# SVR_REVTT_1_4.net
KiCad netlist of a schematic drawn in Altium Designer
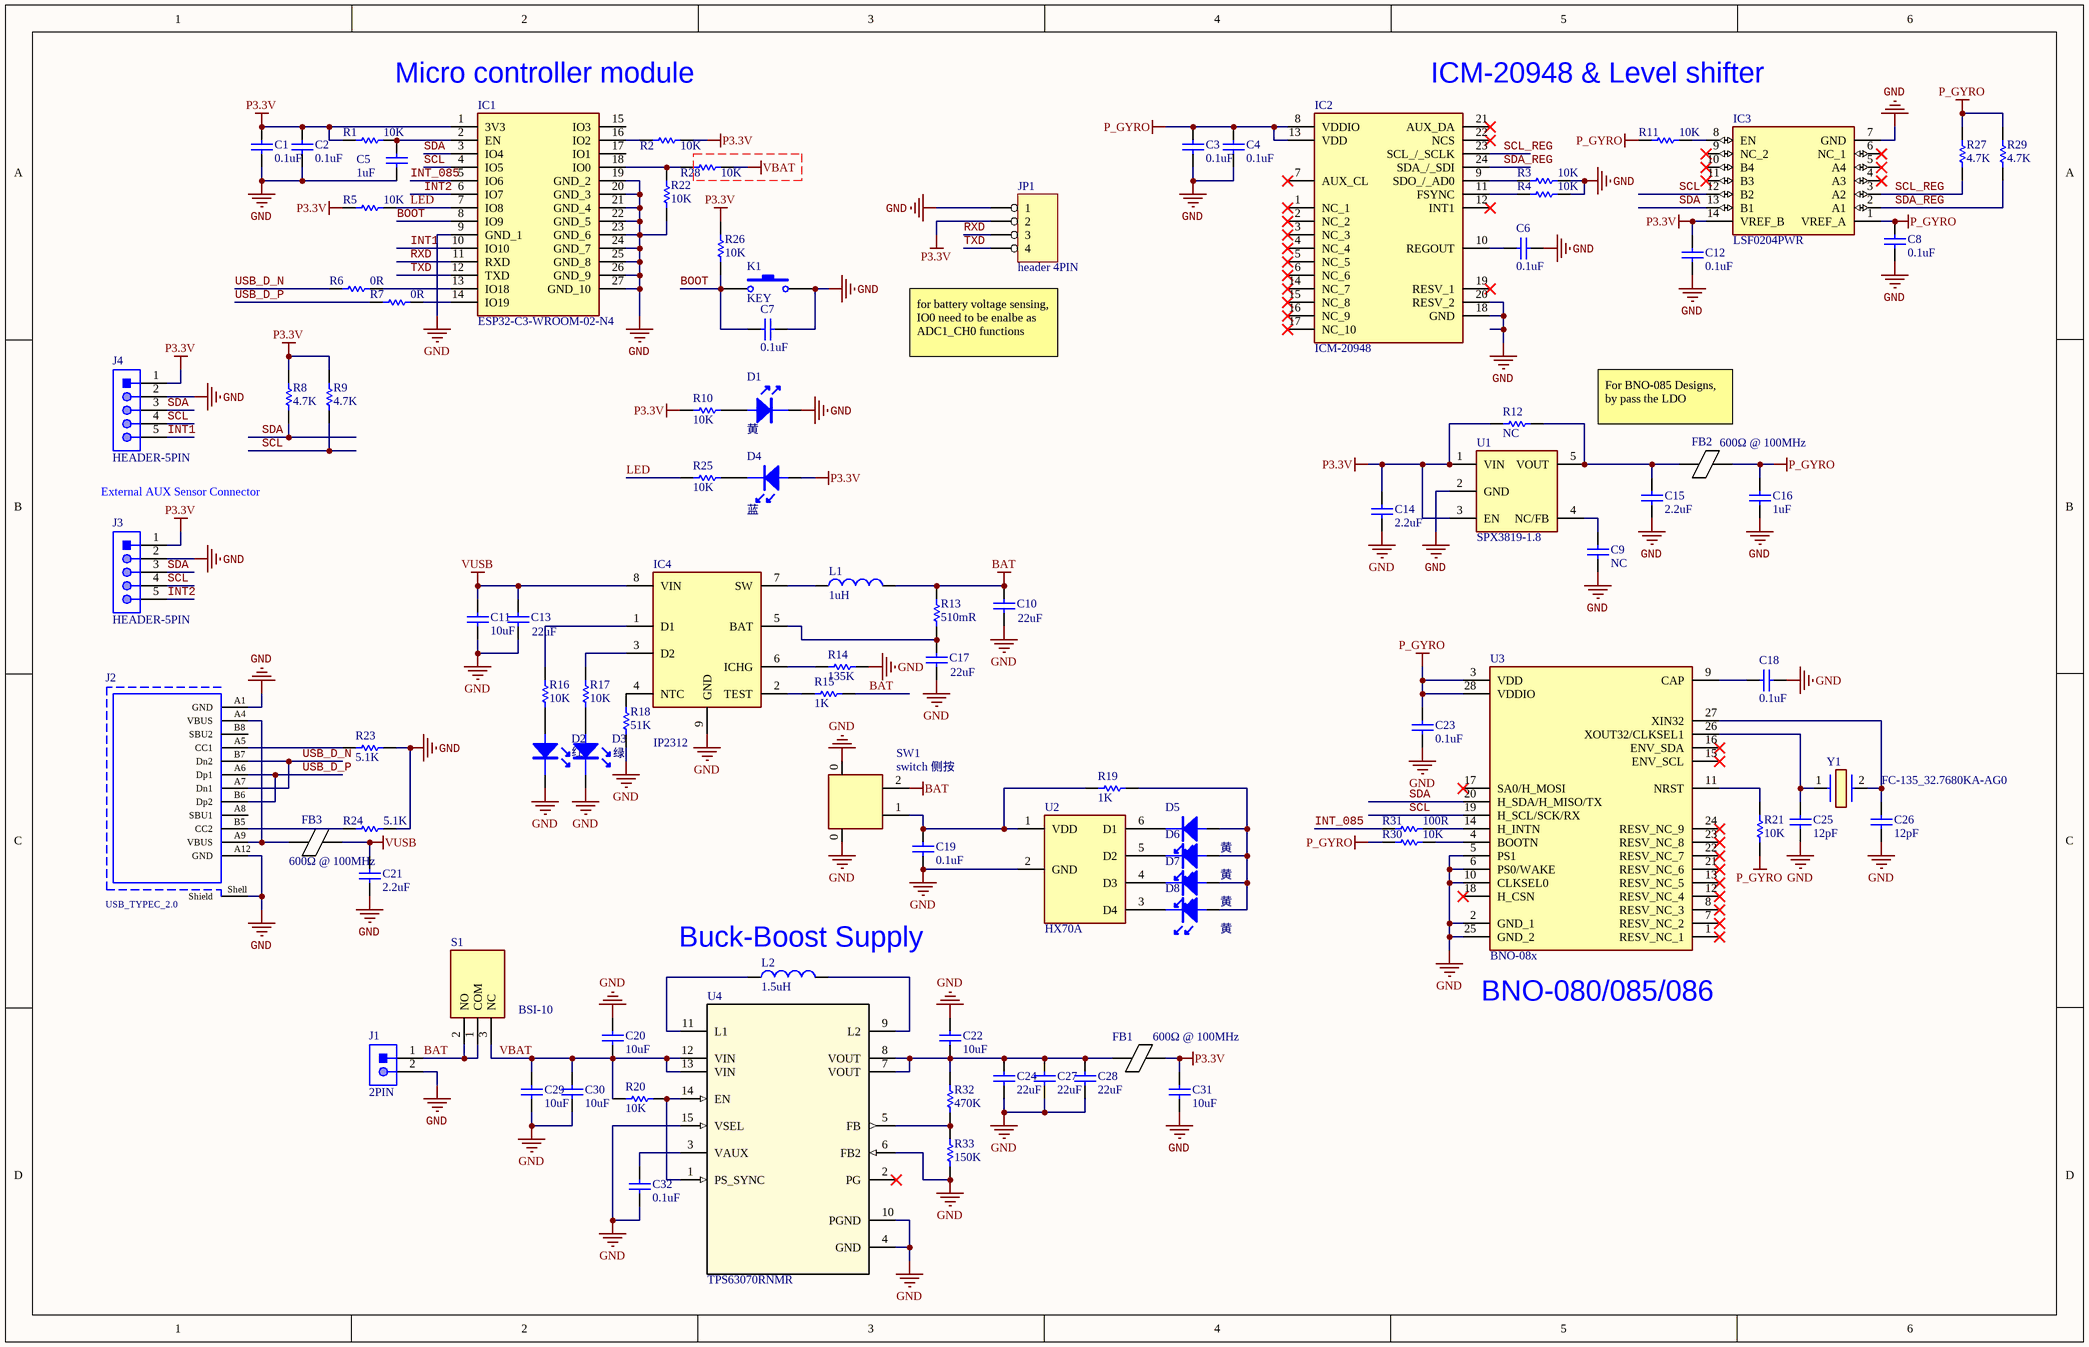
[diagram p0: SVR_REVTT_1.4.SchDoc]

(export (version "E")
  (design (tool "Eeschema 10.0.6"))
  (components
    (comp (ref "C1")
      (value "0.1uF")
      (footprint "0402L")
      (description "Capacitor")
      (fields (field (name "PUBLISHER") "Altium Limited"))
      (libsource (lib "My Footprint") (part "CAP"))
    )
    (comp (ref "C2")
      (value "0.1uF")
      (footprint "0402L")
      (description "Capacitor")
      (fields (field (name "PUBLISHER") "Altium Limited"))
      (libsource (lib "My Footprint") (part "CAP"))
    )
    (comp (ref "C3")
      (value "0.1uF")
      (footprint "0402L")
      (description "Capacitor")
      (fields (field (name "PUBLISHER") "Altium Limited"))
      (libsource (lib "My Footprint") (part "CAP"))
    )
    (comp (ref "C4")
      (value "0.1uF")
      (footprint "0402L")
      (description "Capacitor")
      (fields (field (name "PUBLISHER") "Altium Limited"))
      (libsource (lib "My Footprint") (part "CAP"))
    )
    (comp (ref "C5")
      (value "1uF")
      (footprint "0402L")
      (description "Capacitor")
      (fields (field (name "PUBLISHER") "Altium Limited"))
      (libsource (lib "My Footprint") (part "CAP"))
    )
    (comp (ref "C6")
      (value "0.1uF")
      (footprint "0402L")
      (description "Capacitor")
      (fields (field (name "PUBLISHER") "Altium Limited"))
      (libsource (lib "My Footprint") (part "CAP"))
    )
    (comp (ref "C7")
      (value "0.1uF")
      (footprint "0402L")
      (description "Capacitor")
      (fields (field (name "PUBLISHER") "Altium Limited"))
      (libsource (lib "My Footprint") (part "CAP"))
    )
    (comp (ref "C8")
      (value "0.1uF")
      (footprint "0402L")
      (description "Capacitor")
      (fields (field (name "PUBLISHER") "Altium Limited"))
      (libsource (lib "My Footprint") (part "CAP"))
    )
    (comp (ref "C9")
      (value "NC")
      (footprint "0603_C")
      (description "Capacitor")
      (fields (field (name "PUBLISHER") "Altium Limited"))
      (libsource (lib "My Footprint") (part "CAP"))
    )
    (comp (ref "C10")
      (value "22uF")
      (footprint "0805")
      (description "Capacitor")
      (fields (field (name "PUBLISHER") "Altium Limited"))
      (libsource (lib "My Footprint") (part "CAP"))
    )
    (comp (ref "C11")
      (value "10uF")
      (footprint "0805")
      (description "Capacitor")
      (fields (field (name "PUBLISHER") "Altium Limited"))
      (libsource (lib "My Footprint") (part "CAP"))
    )
    (comp (ref "C12")
      (value "0.1uF")
      (footprint "0402L")
      (description "Capacitor")
      (fields (field (name "PUBLISHER") "Altium Limited"))
      (libsource (lib "My Footprint") (part "CAP"))
    )
    (comp (ref "C13")
      (value "22uF")
      (footprint "0805")
      (description "Capacitor")
      (fields (field (name "PUBLISHER") "Altium Limited"))
      (libsource (lib "My Footprint") (part "CAP"))
    )
    (comp (ref "C14")
      (value "2.2uF")
      (footprint "0603_C")
      (description "Capacitor")
      (fields (field (name "PUBLISHER") "Altium Limited"))
      (libsource (lib "My Footprint") (part "CAP"))
    )
    (comp (ref "C15")
      (value "2.2uF")
      (footprint "0603_C")
      (description "Capacitor")
      (fields (field (name "PUBLISHER") "Altium Limited"))
      (libsource (lib "My Footprint") (part "CAP"))
    )
    (comp (ref "C16")
      (value "1uF")
      (footprint "0603_C")
      (description "Capacitor")
      (fields (field (name "PUBLISHER") "Altium Limited"))
      (libsource (lib "My Footprint") (part "CAP"))
    )
    (comp (ref "C17")
      (value "22uF")
      (footprint "0805")
      (description "Capacitor")
      (fields (field (name "PUBLISHER") "Altium Limited"))
      (libsource (lib "My Footprint") (part "CAP"))
    )
    (comp (ref "C18")
      (value "0.1uF")
      (footprint "0402L")
      (description "Capacitor")
      (fields (field (name "PUBLISHER") "Altium Limited"))
      (libsource (lib "My Footprint") (part "CAP"))
    )
    (comp (ref "C19")
      (value "0.1uF")
      (footprint "0402L")
      (description "Capacitor")
      (fields (field (name "PUBLISHER") "Altium Limited"))
      (libsource (lib "My Footprint") (part "CAP"))
    )
    (comp (ref "C20")
      (value "10uF")
      (footprint "0603_C")
      (description "Capacitor")
      (fields (field (name "PUBLISHER") "Altium Limited"))
      (libsource (lib "My Footprint") (part "CAP"))
    )
    (comp (ref "C21")
      (value "2.2uF")
      (footprint "0603_C")
      (description "Capacitor")
      (fields (field (name "PUBLISHER") "Altium Limited"))
      (libsource (lib "My Footprint") (part "CAP"))
    )
    (comp (ref "C22")
      (value "10uF")
      (footprint "0603_C")
      (description "Capacitor")
      (fields (field (name "PUBLISHER") "Altium Limited"))
      (libsource (lib "My Footprint") (part "CAP"))
    )
    (comp (ref "C23")
      (value "0.1uF")
      (footprint "0402L")
      (description "Capacitor")
      (fields (field (name "PUBLISHER") "Altium Limited"))
      (libsource (lib "My Footprint") (part "CAP"))
    )
    (comp (ref "C24")
      (value "22uF")
      (footprint "0805")
      (description "Capacitor")
      (fields (field (name "PUBLISHER") "Altium Limited"))
      (libsource (lib "My Footprint") (part "CAP"))
    )
    (comp (ref "C25")
      (value "12pF")
      (footprint "0402L")
      (description "Capacitor")
      (fields (field (name "PUBLISHER") "Altium Limited"))
      (libsource (lib "My Footprint") (part "CAP"))
    )
    (comp (ref "C26")
      (value "12pF")
      (footprint "0402L")
      (description "Capacitor")
      (fields (field (name "PUBLISHER") "Altium Limited"))
      (libsource (lib "My Footprint") (part "CAP"))
    )
    (comp (ref "C27")
      (value "22uF")
      (footprint "0805")
      (description "Capacitor")
      (fields (field (name "PUBLISHER") "Altium Limited"))
      (libsource (lib "My Footprint") (part "CAP"))
    )
    (comp (ref "C28")
      (value "22uF")
      (footprint "0805")
      (description "Capacitor")
      (fields (field (name "PUBLISHER") "Altium Limited"))
      (libsource (lib "My Footprint") (part "CAP"))
    )
    (comp (ref "C29")
      (value "10uF")
      (footprint "0805")
      (description "Capacitor")
      (fields (field (name "PUBLISHER") "Altium Limited"))
      (libsource (lib "My Footprint") (part "CAP"))
    )
    (comp (ref "C30")
      (value "10uF")
      (footprint "0805")
      (description "Capacitor")
      (fields (field (name "PUBLISHER") "Altium Limited"))
      (libsource (lib "My Footprint") (part "CAP"))
    )
    (comp (ref "C31")
      (value "10uF")
      (footprint "0805")
      (description "Capacitor")
      (fields (field (name "PUBLISHER") "Altium Limited"))
      (libsource (lib "My Footprint") (part "CAP"))
    )
    (comp (ref "C32")
      (value "0.1uF")
      (footprint "0402L")
      (description "Capacitor")
      (fields (field (name "PUBLISHER") "Altium Limited"))
      (libsource (lib "My Footprint") (part "CAP"))
    )
    (comp (ref "D1")
      (value "黄")
      (footprint "0603_LED")
      (description "LED 发光二极管")
      (libsource (lib "My Footprint") (part "LED"))
    )
    (comp (ref "D2")
      (value "红")
      (footprint "0603_LED")
      (description "LED 发光二极管")
      (libsource (lib "My Footprint") (part "LED"))
    )
    (comp (ref "D3")
      (value "绿")
      (footprint "0603_LED")
      (description "LED 发光二极管")
      (libsource (lib "My Footprint") (part "LED"))
    )
    (comp (ref "D4")
      (value "蓝")
      (footprint "0603_LED")
      (description "LED 发光二极管")
      (libsource (lib "") (part "LED_1"))
    )
    (comp (ref "D5")
      (value "黄")
      (footprint "0603_LED")
      (description "LED 发光二极管")
      (libsource (lib "My Footprint") (part "LED"))
    )
    (comp (ref "D6")
      (value "黄")
      (footprint "0603_LED")
      (description "LED 发光二极管")
      (libsource (lib "My Footprint") (part "LED"))
    )
    (comp (ref "D7")
      (value "黄")
      (footprint "0603_LED")
      (description "LED 发光二极管")
      (libsource (lib "My Footprint") (part "LED"))
    )
    (comp (ref "D8")
      (value "黄")
      (footprint "0603_LED")
      (description "LED 发光二极管")
      (libsource (lib "My Footprint") (part "LED"))
    )
    (comp (ref "FB1")
      (value "600Ω @ 100MHz")
      (footprint "0805")
      (description "磁珠 600Ω @ 100MHz")
      (libsource (lib "My Footprint") (part "FB"))
    )
    (comp (ref "FB2")
      (value "600Ω @ 100MHz")
      (footprint "0603")
      (description "磁珠 600Ω @ 100MHz")
      (libsource (lib "My Footprint") (part "FB"))
    )
    (comp (ref "FB3")
      (value "600Ω @ 100MHz")
      (footprint "0603")
      (description "磁珠 600Ω @ 100MHz")
      (libsource (lib "My Footprint") (part "FB"))
    )
    (comp (ref "IC1")
      (value "ESP32-C3-WROOM-02-N4")
      (footprint "SamacSys:ESP32C3WROOM02N4")
      (description "Integrated Circuit")
      (fields (field (name "MOUSER PART NUMBER") "356-ESP32C3WROOM02N4"))
      (libsource (lib "SamacSys") (part "ESP32-C3-WROOM-02-N4"))
    )
    (comp (ref "IC2")
      (value "ICM-20948")
      (footprint "SamacSys:QFN40P300X300X105-25N-D")
      (description "Integrated Circuit")
      (fields (field (name "MOUSER PART NUMBER") "410-ICM-20948"))
      (libsource (lib "SamacSys") (part "ICM-20948"))
    )
    (comp (ref "IC3")
      (value "LSF0204PWR")
      (footprint "SamacSys:SOP65P640X120-14N")
      (description "Integrated Circuit")
      (fields (field (name "MOUSER PART NUMBER") "595-LSF0204PWR"))
      (libsource (lib "SamacSys") (part "LSF0204PWR"))
    )
    (comp (ref "IC4")
      (value "IP2312")
      (footprint "SOIC-8N")
      (description "Integrated Circuit")
      (libsource (lib "SamacSys") (part "IP2312"))
    )
    (comp (ref "J1")
      (value "2PIN")
      (footprint "XH2.54-WI-2P")
      (libsource (lib "My Footprint") (part "HEADER 2PIN"))
    )
    (comp (ref "J2")
      (value "USB_TYPEC_2.0")
      (footprint "USB_TYPEC_2.0_Horizontal_SMT")
      (description "USB 3.1 Type C Receptacle WR-COM, Horizontal, SMT / THT")
      (fields (field (name "PART NUMBER") "632723300011") (field (name "PUBLISHER") "Wurth Elektronik"))
      (libsource (lib "RegenovoPcbLib") (part "USB_TYPEC_2.0"))
    )
    (comp (ref "J3")
      (value "HEADER-5PIN")
      (footprint "HEADER_5P_1.25_RT")
      (libsource (lib "My Footprint") (part "HEADER-5PIN"))
    )
    (comp (ref "J4")
      (value "HEADER-5PIN")
      (footprint "HEADER_5P_1.25_RT")
      (libsource (lib "My Footprint") (part "HEADER-5PIN"))
    )
    (comp (ref "JP1")
      (value "header 4PIN")
      (footprint "header4")
      (libsource (lib "My Footprint") (part "HEADER 4"))
    )
    (comp (ref "K1")
      (value "KEY")
      (footprint "KEY_2")
      (description "Switch")
      (fields (field (name "PUBLISHER") "Altium Limited"))
      (libsource (lib "My Footprint") (part "KEY_2"))
    )
    (comp (ref "L1")
      (value "1uH")
      (footprint "Inductor  SLO0650")
      (description "电感")
      (fields (field (name "Comment") "INDUCTOR") (field (name "PUBLISHER") "Altium Limited"))
      (libsource (lib "RegenovoPcbLib") (part "INDUCTOR"))
    )
    (comp (ref "L2")
      (value "1.5uH")
      (footprint "Inductor  SMNR4020")
      (description "电感")
      (fields (field (name "Comment") "INDUCTOR") (field (name "PUBLISHER") "Altium Limited"))
      (libsource (lib "RegenovoPcbLib") (part "INDUCTOR"))
    )
    (comp (ref "R1")
      (value "10K")
      (footprint "0402L")
      (description "Resistor")
      (fields (field (name "PUBLISHER") "Altium Limited"))
      (libsource (lib "My Footprint") (part "RES"))
    )
    (comp (ref "R2")
      (value "10K")
      (footprint "0402L")
      (description "Resistor")
      (fields (field (name "PUBLISHER") "Altium Limited"))
      (libsource (lib "My Footprint") (part "RES"))
    )
    (comp (ref "R3")
      (value "10K")
      (footprint "0402L")
      (description "Resistor")
      (fields (field (name "PUBLISHER") "Altium Limited"))
      (libsource (lib "My Footprint") (part "RES"))
    )
    (comp (ref "R4")
      (value "10K")
      (footprint "0402L")
      (description "Resistor")
      (fields (field (name "PUBLISHER") "Altium Limited"))
      (libsource (lib "My Footprint") (part "RES"))
    )
    (comp (ref "R5")
      (value "10K")
      (footprint "0402L")
      (description "Resistor")
      (fields (field (name "PUBLISHER") "Altium Limited"))
      (libsource (lib "My Footprint") (part "RES"))
    )
    (comp (ref "R6")
      (value "0R")
      (footprint "0402L")
      (description "Resistor")
      (fields (field (name "PUBLISHER") "Altium Limited"))
      (libsource (lib "My Footprint") (part "RES"))
    )
    (comp (ref "R7")
      (value "0R")
      (footprint "0402L")
      (description "Resistor")
      (fields (field (name "PUBLISHER") "Altium Limited"))
      (libsource (lib "My Footprint") (part "RES"))
    )
    (comp (ref "R8")
      (value "4.7K")
      (footprint "0402L")
      (description "Resistor")
      (fields (field (name "PUBLISHER") "Altium Limited"))
      (libsource (lib "My Footprint") (part "RES"))
    )
    (comp (ref "R9")
      (value "4.7K")
      (footprint "0402L")
      (description "Resistor")
      (fields (field (name "PUBLISHER") "Altium Limited"))
      (libsource (lib "My Footprint") (part "RES"))
    )
    (comp (ref "R10")
      (value "10K")
      (footprint "0402L")
      (description "Resistor")
      (fields (field (name "PUBLISHER") "Altium Limited"))
      (libsource (lib "My Footprint") (part "RES"))
    )
    (comp (ref "R11")
      (value "10K")
      (footprint "0402L")
      (description "Resistor")
      (fields (field (name "PUBLISHER") "Altium Limited"))
      (libsource (lib "My Footprint") (part "RES"))
    )
    (comp (ref "R12")
      (value "NC")
      (footprint "0603")
      (description "Resistor")
      (fields (field (name "PUBLISHER") "Altium Limited"))
      (libsource (lib "My Footprint") (part "RES"))
    )
    (comp (ref "R13")
      (value "510mR")
      (footprint "0603L")
      (description "Resistor")
      (fields (field (name "PUBLISHER") "Altium Limited"))
      (libsource (lib "My Footprint") (part "RES"))
    )
    (comp (ref "R14")
      (value "135K")
      (footprint "0402L")
      (description "Resistor")
      (fields (field (name "PUBLISHER") "Altium Limited"))
      (libsource (lib "My Footprint") (part "RES"))
    )
    (comp (ref "R15")
      (value "1K")
      (footprint "0402L")
      (description "Resistor")
      (fields (field (name "PUBLISHER") "Altium Limited"))
      (libsource (lib "My Footprint") (part "RES"))
    )
    (comp (ref "R16")
      (value "10K")
      (footprint "0402L")
      (description "Resistor")
      (fields (field (name "PUBLISHER") "Altium Limited"))
      (libsource (lib "My Footprint") (part "RES"))
    )
    (comp (ref "R17")
      (value "10K")
      (footprint "0402L")
      (description "Resistor")
      (fields (field (name "PUBLISHER") "Altium Limited"))
      (libsource (lib "My Footprint") (part "RES"))
    )
    (comp (ref "R18")
      (value "51K")
      (footprint "0402L")
      (description "Resistor")
      (fields (field (name "PUBLISHER") "Altium Limited"))
      (libsource (lib "My Footprint") (part "RES"))
    )
    (comp (ref "R19")
      (value "1K")
      (footprint "0603_R")
      (description "Resistor")
      (fields (field (name "PUBLISHER") "Altium Limited"))
      (libsource (lib "My Footprint") (part "RES"))
    )
    (comp (ref "R20")
      (value "10K")
      (footprint "0402L")
      (description "Resistor")
      (fields (field (name "PUBLISHER") "Altium Limited"))
      (libsource (lib "My Footprint") (part "RES"))
    )
    (comp (ref "R21")
      (value "10K")
      (footprint "0402L")
      (description "Resistor")
      (fields (field (name "PUBLISHER") "Altium Limited"))
      (libsource (lib "My Footprint") (part "RES"))
    )
    (comp (ref "R22")
      (value "10K")
      (footprint "0402L")
      (description "Resistor")
      (fields (field (name "PUBLISHER") "Altium Limited"))
      (libsource (lib "My Footprint") (part "RES"))
    )
    (comp (ref "R23")
      (value "5.1K")
      (footprint "0402L")
      (description "Resistor")
      (fields (field (name "PUBLISHER") "Altium Limited"))
      (libsource (lib "My Footprint") (part "RES"))
    )
    (comp (ref "R24")
      (value "5.1K")
      (footprint "0402L")
      (description "Resistor")
      (fields (field (name "PUBLISHER") "Altium Limited"))
      (libsource (lib "My Footprint") (part "RES"))
    )
    (comp (ref "R25")
      (value "10K")
      (footprint "0402L")
      (description "Resistor")
      (fields (field (name "PUBLISHER") "Altium Limited"))
      (libsource (lib "My Footprint") (part "RES"))
    )
    (comp (ref "R26")
      (value "10K")
      (footprint "0402L")
      (description "Resistor")
      (fields (field (name "PUBLISHER") "Altium Limited"))
      (libsource (lib "My Footprint") (part "RES"))
    )
    (comp (ref "R27")
      (value "4.7K")
      (footprint "0402L")
      (description "Resistor")
      (fields (field (name "PUBLISHER") "Altium Limited"))
      (libsource (lib "My Footprint") (part "RES"))
    )
    (comp (ref "R28")
      (value "10K")
      (footprint "0402L")
      (description "Resistor")
      (fields (field (name "PUBLISHER") "Altium Limited"))
      (libsource (lib "My Footprint") (part "RES"))
    )
    (comp (ref "R29")
      (value "4.7K")
      (footprint "0402L")
      (description "Resistor")
      (fields (field (name "PUBLISHER") "Altium Limited"))
      (libsource (lib "My Footprint") (part "RES"))
    )
    (comp (ref "R30")
      (value "10K")
      (footprint "0402L")
      (description "Resistor")
      (fields (field (name "PUBLISHER") "Altium Limited"))
      (libsource (lib "My Footprint") (part "RES"))
    )
    (comp (ref "R31")
      (value "100R")
      (footprint "0402L")
      (description "Resistor")
      (fields (field (name "PUBLISHER") "Altium Limited"))
      (libsource (lib "My Footprint") (part "RES"))
    )
    (comp (ref "R32")
      (value "470K")
      (footprint "0402L")
      (description "Resistor")
      (fields (field (name "PUBLISHER") "Altium Limited"))
      (libsource (lib "My Footprint") (part "RES"))
    )
    (comp (ref "R33")
      (value "150K")
      (footprint "0402L")
      (description "Resistor")
      (fields (field (name "PUBLISHER") "Altium Limited"))
      (libsource (lib "My Footprint") (part "RES"))
    )
    (comp (ref "S1")
      (value "BSI-10")
      (footprint "BSI10")
      (description "Switch")
      (libsource (lib "SamacSys") (part "BSI-10"))
    )
    (comp (ref "SW1")
      (value "switch 侧按")
      (footprint "TSW 3*6*4.3-S-W")
      (libsource (lib "SamacSys") (part "switch 侧按"))
    )
    (comp (ref "U1")
      (value "SPX3819-1.8")
      (footprint "SOT-23-5")
      (libsource (lib "My Footprint") (part "ADP150"))
    )
    (comp (ref "U2")
      (value "HX70A")
      (footprint "SOT95P250X110-6N")
      (description "单节锂电池电量指示芯片")
      (libsource (lib "SamacSys") (part "HX70A"))
    )
    (comp (ref "U3")
      (value "BNO-08x")
      (footprint "SamacSys:BNO085")
      (description "Accelerometer")
      (fields (field (name "MANUFACTURER_PART_NUMBER") "BNO085"))
      (libsource (lib "SamacSys") (part "BNO085"))
    )
    (comp (ref "U4")
      (value "TPS63070RNMR")
      (footprint "RNM0015A")
      (description "Imported")
      (fields (field (name "MANUFACTURER") "Texas Instruments"))
      (libsource (lib "SamacSys") (part "TPS63070RNMR"))
    )
    (comp (ref "Y1")
      (value "FC-135_32.7680KA-AG0")
      (footprint "SamacSys:FC135327680KAAG0")
      (description "Crystal or Oscillator")
      (fields
        (field (name "MANUFACTURER_PART_NUMBER") "FC-135 32.7680KA-AG0")
        (field (name "MOUSER PART NUMBER") "732-FC135-32.76KAAG0")
      )
      (libsource (lib "SamacSys") (part "FC-135_32.7680KA-AG0"))
    )
  )
  (nets
    (net (code "1") (name "/BOOT") (class "Default")
      (node (ref "C7") (pin "1") (pinfunction "1_1") (pintype "passive"))
      (node (ref "IC1") (pin "8") (pinfunction "IO9_8") (pintype "passive"))
      (node (ref "K1") (pin "1") (pinfunction "1_1") (pintype "passive"))
      (node (ref "R26") (pin "1") (pinfunction "1_1") (pintype "passive"))
    )
    (net (code "2") (name "/INT1") (class "Default")
      (node (ref "IC1") (pin "10") (pinfunction "IO10_10") (pintype "passive"))
      (node (ref "J4") (pin "5") (pinfunction "5_5") (pintype "passive"))
    )
    (net (code "3") (name "/INT2") (class "Default")
      (node (ref "IC1") (pin "6") (pinfunction "IO7_6") (pintype "passive"))
      (node (ref "J3") (pin "5") (pinfunction "5_5") (pintype "passive"))
    )
    (net (code "4") (name "/INT_085") (class "Default")
      (node (ref "IC1") (pin "5") (pinfunction "IO6_5") (pintype "passive"))
      (node (ref "R31") (pin "1") (pinfunction "1_1") (pintype "passive"))
    )
    (net (code "5") (name "/LED") (class "Default")
      (node (ref "IC1") (pin "7") (pinfunction "IO8_7") (pintype "passive"))
      (node (ref "R25") (pin "1") (pinfunction "1_1") (pintype "passive"))
      (node (ref "R5") (pin "2") (pinfunction "2_2") (pintype "passive"))
    )
    (net (code "6") (name "/RXD") (class "Default")
      (node (ref "IC1") (pin "11") (pinfunction "RXD_11") (pintype "passive"))
      (node (ref "JP1") (pin "3") (pinfunction "3_3") (pintype "passive"))
    )
    (net (code "7") (name "/SCL") (class "Default")
      (node (ref "IC1") (pin "4") (pinfunction "IO5_4") (pintype "passive"))
      (node (ref "IC3") (pin "12") (pinfunction "B2_12") (pintype "bidirectional"))
      (node (ref "J3") (pin "4") (pinfunction "4_4") (pintype "passive"))
      (node (ref "J4") (pin "4") (pinfunction "4_4") (pintype "passive"))
      (node (ref "R9") (pin "1") (pinfunction "1_1") (pintype "passive"))
      (node (ref "U3") (pin "19") (pinfunction "H_SCL/SCK/RX_19") (pintype "passive"))
    )
    (net (code "8") (name "/SCL_REG") (class "Default")
      (node (ref "IC2") (pin "23") (pinfunction "SCL_/_SCLK_23") (pintype "passive"))
      (node (ref "IC3") (pin "3") (pinfunction "A2_3") (pintype "bidirectional"))
      (node (ref "R27") (pin "1") (pinfunction "1_1") (pintype "passive"))
    )
    (net (code "9") (name "/SDA") (class "Default")
      (node (ref "IC1") (pin "3") (pinfunction "IO4_3") (pintype "passive"))
      (node (ref "IC3") (pin "13") (pinfunction "B1_13") (pintype "bidirectional"))
      (node (ref "J3") (pin "3") (pinfunction "3_3") (pintype "passive"))
      (node (ref "J4") (pin "3") (pinfunction "3_3") (pintype "passive"))
      (node (ref "R8") (pin "1") (pinfunction "1_1") (pintype "passive"))
      (node (ref "U3") (pin "20") (pinfunction "H_SDA/H_MISO/TX_20") (pintype "passive"))
    )
    (net (code "10") (name "/SDA_REG") (class "Default")
      (node (ref "IC2") (pin "24") (pinfunction "SDA_/_SDI_24") (pintype "passive"))
      (node (ref "IC3") (pin "2") (pinfunction "A1_2") (pintype "bidirectional"))
      (node (ref "R29") (pin "1") (pinfunction "1_1") (pintype "passive"))
    )
    (net (code "11") (name "/TXD") (class "Default")
      (node (ref "IC1") (pin "12") (pinfunction "TXD_12") (pintype "passive"))
      (node (ref "JP1") (pin "4") (pinfunction "4_4") (pintype "passive"))
    )
    (net (code "12") (name "/USB_D_N") (class "Default")
      (node (ref "J2") (pin "A7") (pinfunction "Dn1_A7") (pintype "passive"))
      (node (ref "J2") (pin "B7") (pinfunction "Dn2_B7") (pintype "passive"))
      (node (ref "R6") (pin "1") (pinfunction "1_1") (pintype "passive"))
    )
    (net (code "13") (name "/USB_D_P") (class "Default")
      (node (ref "J2") (pin "A6") (pinfunction "Dp1_A6") (pintype "passive"))
      (node (ref "J2") (pin "B6") (pinfunction "Dp2_B6") (pintype "passive"))
      (node (ref "R7") (pin "1") (pinfunction "1_1") (pintype "passive"))
    )
    (net (code "14") (name "BAT") (class "Default")
      (node (ref "C10") (pin "2") (pinfunction "2_2") (pintype "passive"))
      (node (ref "J1") (pin "1") (pinfunction "1_1") (pintype "passive"))
      (node (ref "L1") (pin "2") (pinfunction "2_2") (pintype "passive"))
      (node (ref "R13") (pin "2") (pinfunction "2_2") (pintype "passive"))
      (node (ref "R15") (pin "2") (pinfunction "2_2") (pintype "passive"))
      (node (ref "S1") (pin "1") (pinfunction "COM_1") (pintype "passive"))
      (node (ref "S1") (pin "2") (pinfunction "NO_2") (pintype "passive"))
      (node (ref "SW1") (pin "2") (pinfunction "2_2") (pintype "passive"))
    )
    (net (code "15") (name "GND") (class "Default")
      (node (ref "C1") (pin "1") (pinfunction "1_1") (pintype "passive"))
      (node (ref "C10") (pin "1") (pinfunction "1_1") (pintype "passive"))
      (node (ref "C11") (pin "1") (pinfunction "1_1") (pintype "passive"))
      (node (ref "C12") (pin "2") (pinfunction "2_2") (pintype "passive"))
      (node (ref "C13") (pin "1") (pinfunction "1_1") (pintype "passive"))
      (node (ref "C14") (pin "1") (pinfunction "1_1") (pintype "passive"))
      (node (ref "C15") (pin "1") (pinfunction "1_1") (pintype "passive"))
      (node (ref "C16") (pin "1") (pinfunction "1_1") (pintype "passive"))
      (node (ref "C17") (pin "1") (pinfunction "1_1") (pintype "passive"))
      (node (ref "C18") (pin "1") (pinfunction "1_1") (pintype "passive"))
      (node (ref "C19") (pin "1") (pinfunction "1_1") (pintype "passive"))
      (node (ref "C2") (pin "1") (pinfunction "1_1") (pintype "passive"))
      (node (ref "C20") (pin "2") (pinfunction "2_2") (pintype "passive"))
      (node (ref "C21") (pin "1") (pinfunction "1_1") (pintype "passive"))
      (node (ref "C22") (pin "2") (pinfunction "2_2") (pintype "passive"))
      (node (ref "C23") (pin "1") (pinfunction "1_1") (pintype "passive"))
      (node (ref "C24") (pin "2") (pinfunction "2_2") (pintype "passive"))
      (node (ref "C25") (pin "1") (pinfunction "1_1") (pintype "passive"))
      (node (ref "C26") (pin "1") (pinfunction "1_1") (pintype "passive"))
      (node (ref "C27") (pin "2") (pinfunction "2_2") (pintype "passive"))
      (node (ref "C28") (pin "2") (pinfunction "2_2") (pintype "passive"))
      (node (ref "C29") (pin "1") (pinfunction "1_1") (pintype "passive"))
      (node (ref "C3") (pin "2") (pinfunction "2_2") (pintype "passive"))
      (node (ref "C30") (pin "1") (pinfunction "1_1") (pintype "passive"))
      (node (ref "C31") (pin "1") (pinfunction "1_1") (pintype "passive"))
      (node (ref "C32") (pin "1") (pinfunction "1_1") (pintype "passive"))
      (node (ref "C4") (pin "2") (pinfunction "2_2") (pintype "passive"))
      (node (ref "C5") (pin "1") (pinfunction "1_1") (pintype "passive"))
      (node (ref "C6") (pin "1") (pinfunction "1_1") (pintype "passive"))
      (node (ref "C7") (pin "2") (pinfunction "2_2") (pintype "passive"))
      (node (ref "C8") (pin "2") (pinfunction "2_2") (pintype "passive"))
      (node (ref "C9") (pin "1") (pinfunction "1_1") (pintype "passive"))
      (node (ref "D1") (pin "1") (pinfunction "K_1") (pintype "passive"))
      (node (ref "D2") (pin "1") (pinfunction "K_1") (pintype "passive"))
      (node (ref "D3") (pin "1") (pinfunction "K_1") (pintype "passive"))
      (node (ref "IC1") (pin "19") (pinfunction "GND_2_19") (pintype "passive"))
      (node (ref "IC1") (pin "20") (pinfunction "GND_3_20") (pintype "passive"))
      (node (ref "IC1") (pin "21") (pinfunction "GND_4_21") (pintype "passive"))
      (node (ref "IC1") (pin "22") (pinfunction "GND_5_22") (pintype "passive"))
      (node (ref "IC1") (pin "23") (pinfunction "GND_6_23") (pintype "passive"))
      (node (ref "IC1") (pin "24") (pinfunction "GND_7_24") (pintype "passive"))
      (node (ref "IC1") (pin "25") (pinfunction "GND_8_25") (pintype "passive"))
      (node (ref "IC1") (pin "26") (pinfunction "GND_9_26") (pintype "passive"))
      (node (ref "IC1") (pin "27") (pinfunction "GND_10_27") (pintype "passive"))
      (node (ref "IC1") (pin "9") (pinfunction "GND_1_9") (pintype "passive"))
      (node (ref "IC2") (pin "18") (pinfunction "GND_18") (pintype "passive"))
      (node (ref "IC2") (pin "20") (pinfunction "RESV_2_20") (pintype "passive"))
      (node (ref "IC3") (pin "7") (pinfunction "GND_7") (pintype "power_in"))
      (node (ref "IC4") (pin "9") (pinfunction "GND_9") (pintype "passive"))
      (node (ref "J1") (pin "2") (pinfunction "2_2") (pintype "passive"))
      (node (ref "J2") (pin "A1") (pinfunction "GND_A1") (pintype "passive"))
      (node (ref "J2") (pin "A12") (pinfunction "GND_A12") (pintype "passive"))
      (node (ref "J2") (pin "Shell") (pinfunction "Shield_Shell") (pintype "passive"))
      (node (ref "J3") (pin "2") (pinfunction "2_2") (pintype "passive"))
      (node (ref "J4") (pin "2") (pinfunction "2_2") (pintype "passive"))
      (node (ref "JP1") (pin "1") (pinfunction "1_1") (pintype "passive"))
      (node (ref "K1") (pin "2") (pinfunction "2_2") (pintype "passive"))
      (node (ref "R14") (pin "2") (pinfunction "2_2") (pintype "passive"))
      (node (ref "R18") (pin "1") (pinfunction "1_1") (pintype "passive"))
      (node (ref "R22") (pin "1") (pinfunction "1_1") (pintype "passive"))
      (node (ref "R23") (pin "2") (pinfunction "2_2") (pintype "passive"))
      (node (ref "R24") (pin "2") (pinfunction "2_2") (pintype "passive"))
      (node (ref "R3") (pin "2") (pinfunction "2_2") (pintype "passive"))
      (node (ref "R33") (pin "1") (pinfunction "1_1") (pintype "passive"))
      (node (ref "R4") (pin "2") (pinfunction "2_2") (pintype "passive"))
      (node (ref "SW1") (pin "0") (pinfunction "0_0") (pintype "passive"))
      (node (ref "U1") (pin "2") (pinfunction "GND_2") (pintype "passive"))
      (node (ref "U2") (pin "2") (pinfunction "GND_2") (pintype "passive"))
      (node (ref "U3") (pin "10") (pinfunction "CLKSEL0_10") (pintype "passive"))
      (node (ref "U3") (pin "2") (pinfunction "GND_1_2") (pintype "passive"))
      (node (ref "U3") (pin "25") (pinfunction "GND_2_25") (pintype "passive"))
      (node (ref "U3") (pin "5") (pinfunction "PS1_5") (pintype "passive"))
      (node (ref "U3") (pin "6") (pinfunction "PS0/WAKE_6") (pintype "passive"))
      (node (ref "U4") (pin "10") (pinfunction "PGND_10") (pintype "power_in"))
      (node (ref "U4") (pin "15") (pinfunction "VSEL_15") (pintype "input"))
      (node (ref "U4") (pin "4") (pinfunction "GND_4") (pintype "power_in"))
      (node (ref "U4") (pin "6") (pinfunction "FB2_6") (pintype "input"))
    )
    (net (code "16") (name "Net-(C22-Pad1)") (class "Default")
      (node (ref "C22") (pin "1") (pinfunction "1_1") (pintype "passive"))
      (node (ref "C24") (pin "1") (pinfunction "1_1") (pintype "passive"))
      (node (ref "C27") (pin "1") (pinfunction "1_1") (pintype "passive"))
      (node (ref "C28") (pin "1") (pinfunction "1_1") (pintype "passive"))
      (node (ref "FB1") (pin "1") (pinfunction "1_1") (pintype "passive"))
      (node (ref "R32") (pin "2") (pinfunction "2_2") (pintype "passive"))
      (node (ref "U4") (pin "7") (pinfunction "VOUT_7") (pintype "power_in"))
      (node (ref "U4") (pin "8") (pinfunction "VOUT_8") (pintype "power_in"))
    )
    (net (code "17") (name "Net-(D1-A)") (class "Default")
      (node (ref "D1") (pin "2") (pinfunction "A_2") (pintype "passive"))
      (node (ref "R10") (pin "2") (pinfunction "2_2") (pintype "passive"))
    )
    (net (code "18") (name "Net-(D2-A)") (class "Default")
      (node (ref "D2") (pin "2") (pinfunction "A_2") (pintype "passive"))
      (node (ref "R16") (pin "1") (pinfunction "1_1") (pintype "passive"))
    )
    (net (code "19") (name "Net-(D3-A)") (class "Default")
      (node (ref "D3") (pin "2") (pinfunction "A_2") (pintype "passive"))
      (node (ref "R17") (pin "1") (pinfunction "1_1") (pintype "passive"))
    )
    (net (code "20") (name "Net-(D4-A-Pad2)") (class "Default")
      (node (ref "D4") (pin "2") (pinfunction "A_2") (pintype "passive"))
      (node (ref "R25") (pin "2") (pinfunction "2_2") (pintype "passive"))
    )
    (net (code "21") (name "Net-(D5-A)") (class "Default")
      (node (ref "D5") (pin "2") (pinfunction "A_2") (pintype "passive"))
      (node (ref "D6") (pin "2") (pinfunction "A_2") (pintype "passive"))
      (node (ref "D7") (pin "2") (pinfunction "A_2") (pintype "passive"))
      (node (ref "D8") (pin "2") (pinfunction "A_2") (pintype "passive"))
      (node (ref "R19") (pin "2") (pinfunction "2_2") (pintype "passive"))
    )
    (net (code "22") (name "Net-(D5-K)") (class "Default")
      (node (ref "D5") (pin "1") (pinfunction "K_1") (pintype "passive"))
      (node (ref "U2") (pin "6") (pinfunction "D1_6") (pintype "passive"))
    )
    (net (code "23") (name "Net-(D6-K)") (class "Default")
      (node (ref "D6") (pin "1") (pinfunction "K_1") (pintype "passive"))
      (node (ref "U2") (pin "5") (pinfunction "D2_5") (pintype "passive"))
    )
    (net (code "24") (name "Net-(D7-K)") (class "Default")
      (node (ref "D7") (pin "1") (pinfunction "K_1") (pintype "passive"))
      (node (ref "U2") (pin "4") (pinfunction "D3_4") (pintype "passive"))
    )
    (net (code "25") (name "Net-(D8-K)") (class "Default")
      (node (ref "D8") (pin "1") (pinfunction "K_1") (pintype "passive"))
      (node (ref "U2") (pin "3") (pinfunction "D4_3") (pintype "passive"))
    )
    (net (code "26") (name "Net-(FB3-Pad1)") (class "Default")
      (node (ref "FB3") (pin "1") (pinfunction "1_1") (pintype "passive"))
      (node (ref "J2") (pin "A4") (pinfunction "VBUS_A4") (pintype "passive"))
      (node (ref "J2") (pin "A9") (pinfunction "VBUS_A9") (pintype "passive"))
    )
    (net (code "27") (name "Net-(IC1-EN)") (class "Default")
      (node (ref "C5") (pin "2") (pinfunction "2_2") (pintype "passive"))
      (node (ref "IC1") (pin "2") (pinfunction "EN_2") (pintype "passive"))
      (node (ref "R1") (pin "2") (pinfunction "2_2") (pintype "passive"))
    )
    (net (code "28") (name "Net-(IC1-IO0)") (class "Default")
      (node (ref "IC1") (pin "18") (pinfunction "IO0_18") (pintype "passive"))
      (node (ref "R22") (pin "2") (pinfunction "2_2") (pintype "passive"))
      (node (ref "R28") (pin "1") (pinfunction "1_1") (pintype "passive"))
    )
    (net (code "29") (name "Net-(IC1-IO2)") (class "Default")
      (node (ref "IC1") (pin "16") (pinfunction "IO2_16") (pintype "passive"))
      (node (ref "R2") (pin "1") (pinfunction "1_1") (pintype "passive"))
    )
    (net (code "30") (name "Net-(IC1-IO18)") (class "Default")
      (node (ref "IC1") (pin "13") (pinfunction "IO18_13") (pintype "passive"))
      (node (ref "R6") (pin "2") (pinfunction "2_2") (pintype "passive"))
    )
    (net (code "31") (name "Net-(IC1-IO19)") (class "Default")
      (node (ref "IC1") (pin "14") (pinfunction "IO19_14") (pintype "passive"))
      (node (ref "R7") (pin "2") (pinfunction "2_2") (pintype "passive"))
    )
    (net (code "32") (name "Net-(IC2-FSYNC)") (class "Default")
      (node (ref "IC2") (pin "11") (pinfunction "FSYNC_11") (pintype "passive"))
      (node (ref "R4") (pin "1") (pinfunction "1_1") (pintype "passive"))
    )
    (net (code "33") (name "Net-(IC2-REGOUT)") (class "Default")
      (node (ref "C6") (pin "2") (pinfunction "2_2") (pintype "passive"))
      (node (ref "IC2") (pin "10") (pinfunction "REGOUT_10") (pintype "passive"))
    )
    (net (code "34") (name "Net-(IC2-SDO_{slash}_AD0)") (class "Default")
      (node (ref "IC2") (pin "9") (pinfunction "SDO_/_AD0_9") (pintype "passive"))
      (node (ref "R3") (pin "1") (pinfunction "1_1") (pintype "passive"))
    )
    (net (code "35") (name "Net-(IC3-EN)") (class "Default")
      (node (ref "IC3") (pin "8") (pinfunction "EN_8") (pintype "bidirectional"))
      (node (ref "R11") (pin "2") (pinfunction "2_2") (pintype "passive"))
    )
    (net (code "36") (name "Net-(IC4-BAT)") (class "Default")
      (node (ref "C17") (pin "2") (pinfunction "2_2") (pintype "passive"))
      (node (ref "IC4") (pin "5") (pinfunction "BAT_5") (pintype "passive"))
      (node (ref "R13") (pin "1") (pinfunction "1_1") (pintype "passive"))
    )
    (net (code "37") (name "Net-(IC4-D1)") (class "Default")
      (node (ref "IC4") (pin "1") (pinfunction "D1_1") (pintype "passive"))
      (node (ref "R16") (pin "2") (pinfunction "2_2") (pintype "passive"))
    )
    (net (code "38") (name "Net-(IC4-D2)") (class "Default")
      (node (ref "IC4") (pin "3") (pinfunction "D2_3") (pintype "passive"))
      (node (ref "R17") (pin "2") (pinfunction "2_2") (pintype "passive"))
    )
    (net (code "39") (name "Net-(IC4-ICHG)") (class "Default")
      (node (ref "IC4") (pin "6") (pinfunction "ICHG_6") (pintype "passive"))
      (node (ref "R14") (pin "1") (pinfunction "1_1") (pintype "passive"))
    )
    (net (code "40") (name "Net-(IC4-NTC)") (class "Default")
      (node (ref "IC4") (pin "4") (pinfunction "NTC_4") (pintype "passive"))
      (node (ref "R18") (pin "2") (pinfunction "2_2") (pintype "passive"))
    )
    (net (code "41") (name "Net-(IC4-SW)") (class "Default")
      (node (ref "IC4") (pin "7") (pinfunction "SW_7") (pintype "passive"))
      (node (ref "L1") (pin "1") (pinfunction "1_1") (pintype "passive"))
    )
    (net (code "42") (name "Net-(IC4-TEST)") (class "Default")
      (node (ref "IC4") (pin "2") (pinfunction "TEST_2") (pintype "passive"))
      (node (ref "R15") (pin "1") (pinfunction "1_1") (pintype "passive"))
    )
    (net (code "43") (name "Net-(J2-CC1)") (class "Default")
      (node (ref "J2") (pin "A5") (pinfunction "CC1_A5") (pintype "passive"))
      (node (ref "R23") (pin "1") (pinfunction "1_1") (pintype "passive"))
    )
    (net (code "44") (name "Net-(J2-CC2)") (class "Default")
      (node (ref "J2") (pin "B5") (pinfunction "CC2_B5") (pintype "passive"))
      (node (ref "R24") (pin "1") (pinfunction "1_1") (pintype "passive"))
    )
    (net (code "45") (name "Net-(U1-NC{slash}FB)") (class "Default")
      (node (ref "C9") (pin "2") (pinfunction "2_2") (pintype "passive"))
      (node (ref "U1") (pin "4") (pinfunction "NC/FB_4") (pintype "passive"))
    )
    (net (code "46") (name "Net-(U1-VOUT)") (class "Default")
      (node (ref "C15") (pin "2") (pinfunction "2_2") (pintype "passive"))
      (node (ref "FB2") (pin "1") (pinfunction "1_1") (pintype "passive"))
      (node (ref "R12") (pin "1") (pinfunction "1_1") (pintype "passive"))
      (node (ref "U1") (pin "5") (pinfunction "VOUT_5") (pintype "passive"))
    )
    (net (code "47") (name "Net-(U2-VDD)") (class "Default")
      (node (ref "C19") (pin "2") (pinfunction "2_2") (pintype "passive"))
      (node (ref "R19") (pin "1") (pinfunction "1_1") (pintype "passive"))
      (node (ref "SW1") (pin "1") (pinfunction "1_1") (pintype "passive"))
      (node (ref "U2") (pin "1") (pinfunction "VDD_1") (pintype "passive"))
    )
    (net (code "48") (name "Net-(U3-BOOTN)") (class "Default")
      (node (ref "R30") (pin "2") (pinfunction "2_2") (pintype "passive"))
      (node (ref "U3") (pin "4") (pinfunction "BOOTN_4") (pintype "passive"))
    )
    (net (code "49") (name "Net-(U3-CAP)") (class "Default")
      (node (ref "C18") (pin "2") (pinfunction "2_2") (pintype "passive"))
      (node (ref "U3") (pin "9") (pinfunction "CAP_9") (pintype "passive"))
    )
    (net (code "50") (name "Net-(U3-H_INTN)") (class "Default")
      (node (ref "R31") (pin "2") (pinfunction "2_2") (pintype "passive"))
      (node (ref "U3") (pin "14") (pinfunction "H_INTN_14") (pintype "passive"))
    )
    (net (code "51") (name "Net-(U3-NRST)") (class "Default")
      (node (ref "R21") (pin "2") (pinfunction "2_2") (pintype "passive"))
      (node (ref "U3") (pin "11") (pinfunction "NRST_11") (pintype "passive"))
    )
    (net (code "52") (name "Net-(U3-XIN32)") (class "Default")
      (node (ref "C26") (pin "2") (pinfunction "2_2") (pintype "passive"))
      (node (ref "U3") (pin "27") (pinfunction "XIN32_27") (pintype "passive"))
      (node (ref "Y1") (pin "2") (pinfunction "CRYSTAL_2_2") (pintype "passive"))
    )
    (net (code "53") (name "Net-(U3-XOUT32{slash}CLKSEL1)") (class "Default")
      (node (ref "C25") (pin "2") (pinfunction "2_2") (pintype "passive"))
      (node (ref "U3") (pin "26") (pinfunction "XOUT32/CLKSEL1_26") (pintype "passive"))
      (node (ref "Y1") (pin "1") (pinfunction "1_1") (pintype "passive"))
    )
    (net (code "54") (name "Net-(U4-EN)") (class "Default")
      (node (ref "R20") (pin "2") (pinfunction "2_2") (pintype "passive"))
      (node (ref "U4") (pin "1") (pinfunction "PS_SYNC_1") (pintype "input"))
      (node (ref "U4") (pin "14") (pinfunction "EN_14") (pintype "input"))
    )
    (net (code "55") (name "Net-(U4-FB)") (class "Default")
      (node (ref "R32") (pin "1") (pinfunction "1_1") (pintype "passive"))
      (node (ref "R33") (pin "2") (pinfunction "2_2") (pintype "passive"))
      (node (ref "U4") (pin "5") (pinfunction "FB_5") (pintype "output"))
    )
    (net (code "56") (name "Net-(U4-L1)") (class "Default")
      (node (ref "L2") (pin "1") (pinfunction "1_1") (pintype "passive"))
      (node (ref "U4") (pin "11") (pinfunction "L1_11") (pintype "passive"))
    )
    (net (code "57") (name "Net-(U4-L2)") (class "Default")
      (node (ref "L2") (pin "2") (pinfunction "2_2") (pintype "passive"))
      (node (ref "U4") (pin "9") (pinfunction "L2_9") (pintype "passive"))
    )
    (net (code "58") (name "Net-(U4-VAUX)") (class "Default")
      (node (ref "C32") (pin "2") (pinfunction "2_2") (pintype "passive"))
      (node (ref "U4") (pin "3") (pinfunction "VAUX_3") (pintype "passive"))
    )
    (net (code "59") (name "P3.3V") (class "Default")
      (node (ref "C1") (pin "2") (pinfunction "2_2") (pintype "passive"))
      (node (ref "C12") (pin "1") (pinfunction "1_1") (pintype "passive"))
      (node (ref "C14") (pin "2") (pinfunction "2_2") (pintype "passive"))
      (node (ref "C2") (pin "2") (pinfunction "2_2") (pintype "passive"))
      (node (ref "C31") (pin "2") (pinfunction "2_2") (pintype "passive"))
      (node (ref "D4") (pin "1") (pinfunction "A_1") (pintype "passive"))
      (node (ref "FB1") (pin "2") (pinfunction "2_2") (pintype "passive"))
      (node (ref "IC1") (pin "1") (pinfunction "3V3_1") (pintype "passive"))
      (node (ref "IC3") (pin "14") (pinfunction "VREF_B_14") (pintype "power_in"))
      (node (ref "J3") (pin "1") (pinfunction "1_1") (pintype "passive"))
      (node (ref "J4") (pin "1") (pinfunction "1_1") (pintype "passive"))
      (node (ref "JP1") (pin "2") (pinfunction "2_2") (pintype "passive"))
      (node (ref "R1") (pin "1") (pinfunction "1_1") (pintype "passive"))
      (node (ref "R10") (pin "1") (pinfunction "1_1") (pintype "passive"))
      (node (ref "R12") (pin "2") (pinfunction "2_2") (pintype "passive"))
      (node (ref "R2") (pin "2") (pinfunction "2_2") (pintype "passive"))
      (node (ref "R26") (pin "2") (pinfunction "2_2") (pintype "passive"))
      (node (ref "R5") (pin "1") (pinfunction "1_1") (pintype "passive"))
      (node (ref "R8") (pin "2") (pinfunction "2_2") (pintype "passive"))
      (node (ref "R9") (pin "2") (pinfunction "2_2") (pintype "passive"))
      (node (ref "U1") (pin "1") (pinfunction "VIN_1") (pintype "passive"))
      (node (ref "U1") (pin "3") (pinfunction "EN_3") (pintype "passive"))
    )
    (net (code "60") (name "P_GYRO") (class "Default")
      (node (ref "C16") (pin "2") (pinfunction "2_2") (pintype "passive"))
      (node (ref "C23") (pin "2") (pinfunction "2_2") (pintype "passive"))
      (node (ref "C3") (pin "1") (pinfunction "1_1") (pintype "passive"))
      (node (ref "C4") (pin "1") (pinfunction "1_1") (pintype "passive"))
      (node (ref "C8") (pin "1") (pinfunction "1_1") (pintype "passive"))
      (node (ref "FB2") (pin "2") (pinfunction "2_2") (pintype "passive"))
      (node (ref "IC2") (pin "13") (pinfunction "VDD_13") (pintype "passive"))
      (node (ref "IC2") (pin "8") (pinfunction "VDDIO_8") (pintype "passive"))
      (node (ref "IC3") (pin "1") (pinfunction "VREF_A_1") (pintype "power_in"))
      (node (ref "R11") (pin "1") (pinfunction "1_1") (pintype "passive"))
      (node (ref "R21") (pin "1") (pinfunction "1_1") (pintype "passive"))
      (node (ref "R27") (pin "2") (pinfunction "2_2") (pintype "passive"))
      (node (ref "R29") (pin "2") (pinfunction "2_2") (pintype "passive"))
      (node (ref "R30") (pin "1") (pinfunction "1_1") (pintype "passive"))
      (node (ref "U3") (pin "28") (pinfunction "VDDIO_28") (pintype "passive"))
      (node (ref "U3") (pin "3") (pinfunction "VDD_3") (pintype "passive"))
    )
    (net (code "61") (name "VBAT") (class "Default")
      (node (ref "C20") (pin "1") (pinfunction "1_1") (pintype "passive"))
      (node (ref "C29") (pin "2") (pinfunction "2_2") (pintype "passive"))
      (node (ref "C30") (pin "2") (pinfunction "2_2") (pintype "passive"))
      (node (ref "R20") (pin "1") (pinfunction "1_1") (pintype "passive"))
      (node (ref "R28") (pin "2") (pinfunction "2_2") (pintype "passive"))
      (node (ref "S1") (pin "3") (pinfunction "NC_3") (pintype "passive"))
      (node (ref "U4") (pin "12") (pinfunction "VIN_12") (pintype "power_in"))
      (node (ref "U4") (pin "13") (pinfunction "VIN_13") (pintype "power_in"))
    )
    (net (code "62") (name "VUSB") (class "Default")
      (node (ref "C11") (pin "2") (pinfunction "2_2") (pintype "passive"))
      (node (ref "C13") (pin "2") (pinfunction "2_2") (pintype "passive"))
      (node (ref "C21") (pin "2") (pinfunction "2_2") (pintype "passive"))
      (node (ref "FB3") (pin "2") (pinfunction "2_2") (pintype "passive"))
      (node (ref "IC4") (pin "8") (pinfunction "VIN_8") (pintype "passive"))
    )
    (net (code "63") (name "unconnected-(IC1-IO1-Pad17)") (class "Default")
      (node (ref "IC1") (pin "17") (pinfunction "IO1_17") (pintype "passive"))
    )
    (net (code "64") (name "unconnected-(IC1-IO3-Pad15)") (class "Default")
      (node (ref "IC1") (pin "15") (pinfunction "IO3_15") (pintype "passive"))
    )
    (net (code "65") (name "unconnected-(IC2-AUX_CL-Pad7)") (class "Default")
      (node (ref "IC2") (pin "7") (pinfunction "AUX_CL_7") (pintype "passive+no_connect"))
    )
    (net (code "66") (name "unconnected-(IC2-AUX_DA-Pad21)") (class "Default")
      (node (ref "IC2") (pin "21") (pinfunction "AUX_DA_21") (pintype "passive+no_connect"))
    )
    (net (code "67") (name "unconnected-(IC2-INT1-Pad12)") (class "Default")
      (node (ref "IC2") (pin "12") (pinfunction "INT1_12") (pintype "passive+no_connect"))
    )
    (net (code "68") (name "unconnected-(IC2-NCS-Pad22)") (class "Default")
      (node (ref "IC2") (pin "22") (pinfunction "NCS_22") (pintype "passive+no_connect"))
    )
    (net (code "69") (name "unconnected-(IC2-NC_1-Pad1)") (class "Default")
      (node (ref "IC2") (pin "1") (pinfunction "NC_1_1") (pintype "passive+no_connect"))
    )
    (net (code "70") (name "unconnected-(IC2-NC_2-Pad2)") (class "Default")
      (node (ref "IC2") (pin "2") (pinfunction "NC_2_2") (pintype "passive+no_connect"))
    )
    (net (code "71") (name "unconnected-(IC2-NC_3-Pad3)") (class "Default")
      (node (ref "IC2") (pin "3") (pinfunction "NC_3_3") (pintype "passive+no_connect"))
    )
    (net (code "72") (name "unconnected-(IC2-NC_4-Pad4)") (class "Default")
      (node (ref "IC2") (pin "4") (pinfunction "NC_4_4") (pintype "passive+no_connect"))
    )
    (net (code "73") (name "unconnected-(IC2-NC_5-Pad5)") (class "Default")
      (node (ref "IC2") (pin "5") (pinfunction "NC_5_5") (pintype "passive+no_connect"))
    )
    (net (code "74") (name "unconnected-(IC2-NC_6-Pad6)") (class "Default")
      (node (ref "IC2") (pin "6") (pinfunction "NC_6_6") (pintype "passive+no_connect"))
    )
    (net (code "75") (name "unconnected-(IC2-NC_7-Pad14)") (class "Default")
      (node (ref "IC2") (pin "14") (pinfunction "NC_7_14") (pintype "passive+no_connect"))
    )
    (net (code "76") (name "unconnected-(IC2-NC_8-Pad15)") (class "Default")
      (node (ref "IC2") (pin "15") (pinfunction "NC_8_15") (pintype "passive+no_connect"))
    )
    (net (code "77") (name "unconnected-(IC2-NC_9-Pad16)") (class "Default")
      (node (ref "IC2") (pin "16") (pinfunction "NC_9_16") (pintype "passive+no_connect"))
    )
    (net (code "78") (name "unconnected-(IC2-NC_10-Pad17)") (class "Default")
      (node (ref "IC2") (pin "17") (pinfunction "NC_10_17") (pintype "passive+no_connect"))
    )
    (net (code "79") (name "unconnected-(IC2-RESV_1-Pad19)") (class "Default")
      (node (ref "IC2") (pin "19") (pinfunction "RESV_1_19") (pintype "passive+no_connect"))
    )
    (net (code "80") (name "unconnected-(IC3-A3-Pad4)") (class "Default")
      (node (ref "IC3") (pin "4") (pinfunction "A3_4") (pintype "bidirectional+no_connect"))
    )
    (net (code "81") (name "unconnected-(IC3-A4-Pad5)") (class "Default")
      (node (ref "IC3") (pin "5") (pinfunction "A4_5") (pintype "bidirectional+no_connect"))
    )
    (net (code "82") (name "unconnected-(IC3-B3-Pad11)") (class "Default")
      (node (ref "IC3") (pin "11") (pinfunction "B3_11") (pintype "bidirectional+no_connect"))
    )
    (net (code "83") (name "unconnected-(IC3-B4-Pad10)") (class "Default")
      (node (ref "IC3") (pin "10") (pinfunction "B4_10") (pintype "bidirectional+no_connect"))
    )
    (net (code "84") (name "unconnected-(IC3-NC_1-Pad6)") (class "Default")
      (node (ref "IC3") (pin "6") (pinfunction "NC_1_6") (pintype "bidirectional+no_connect"))
    )
    (net (code "85") (name "unconnected-(IC3-NC_2-Pad9)") (class "Default")
      (node (ref "IC3") (pin "9") (pinfunction "NC_2_9") (pintype "bidirectional+no_connect"))
    )
    (net (code "86") (name "unconnected-(J2-SBU1-PadA8)") (class "Default")
      (node (ref "J2") (pin "A8") (pinfunction "SBU1_A8") (pintype "passive"))
    )
    (net (code "87") (name "unconnected-(J2-SBU2-PadB8)") (class "Default")
      (node (ref "J2") (pin "B8") (pinfunction "SBU2_B8") (pintype "passive"))
    )
    (net (code "88") (name "unconnected-(U3-ENV_SCL-Pad15)") (class "Default")
      (node (ref "U3") (pin "15") (pinfunction "ENV_SCL_15") (pintype "passive+no_connect"))
    )
    (net (code "89") (name "unconnected-(U3-ENV_SDA-Pad16)") (class "Default")
      (node (ref "U3") (pin "16") (pinfunction "ENV_SDA_16") (pintype "passive+no_connect"))
    )
    (net (code "90") (name "unconnected-(U3-H_CSN-Pad18)") (class "Default")
      (node (ref "U3") (pin "18") (pinfunction "H_CSN_18") (pintype "passive+no_connect"))
    )
    (net (code "91") (name "unconnected-(U3-RESV_NC_1-Pad1)") (class "Default")
      (node (ref "U3") (pin "1") (pinfunction "RESV_NC_1_1") (pintype "passive+no_connect"))
    )
    (net (code "92") (name "unconnected-(U3-RESV_NC_2-Pad7)") (class "Default")
      (node (ref "U3") (pin "7") (pinfunction "RESV_NC_2_7") (pintype "passive+no_connect"))
    )
    (net (code "93") (name "unconnected-(U3-RESV_NC_3-Pad8)") (class "Default")
      (node (ref "U3") (pin "8") (pinfunction "RESV_NC_3_8") (pintype "passive+no_connect"))
    )
    (net (code "94") (name "unconnected-(U3-RESV_NC_4-Pad12)") (class "Default")
      (node (ref "U3") (pin "12") (pinfunction "RESV_NC_4_12") (pintype "passive+no_connect"))
    )
    (net (code "95") (name "unconnected-(U3-RESV_NC_5-Pad13)") (class "Default")
      (node (ref "U3") (pin "13") (pinfunction "RESV_NC_5_13") (pintype "passive+no_connect"))
    )
    (net (code "96") (name "unconnected-(U3-RESV_NC_6-Pad21)") (class "Default")
      (node (ref "U3") (pin "21") (pinfunction "RESV_NC_6_21") (pintype "passive+no_connect"))
    )
    (net (code "97") (name "unconnected-(U3-RESV_NC_7-Pad22)") (class "Default")
      (node (ref "U3") (pin "22") (pinfunction "RESV_NC_7_22") (pintype "passive+no_connect"))
    )
    (net (code "98") (name "unconnected-(U3-RESV_NC_8-Pad23)") (class "Default")
      (node (ref "U3") (pin "23") (pinfunction "RESV_NC_8_23") (pintype "passive+no_connect"))
    )
    (net (code "99") (name "unconnected-(U3-RESV_NC_9-Pad24)") (class "Default")
      (node (ref "U3") (pin "24") (pinfunction "RESV_NC_9_24") (pintype "passive+no_connect"))
    )
    (net (code "100") (name "unconnected-(U3-SA0{slash}H_MOSI-Pad17)") (class "Default")
      (node (ref "U3") (pin "17") (pinfunction "SA0/H_MOSI_17") (pintype "passive+no_connect"))
    )
    (net (code "101") (name "unconnected-(U4-PG-Pad2)") (class "Default")
      (node (ref "U4") (pin "2") (pinfunction "PG_2") (pintype "open_collector+no_connect"))
    )
  )
)
